# OSO-SCAP-A1-02_SAMD51_Sensor_Cap.net
KiCad netlist of a schematic drawn in EAGLE
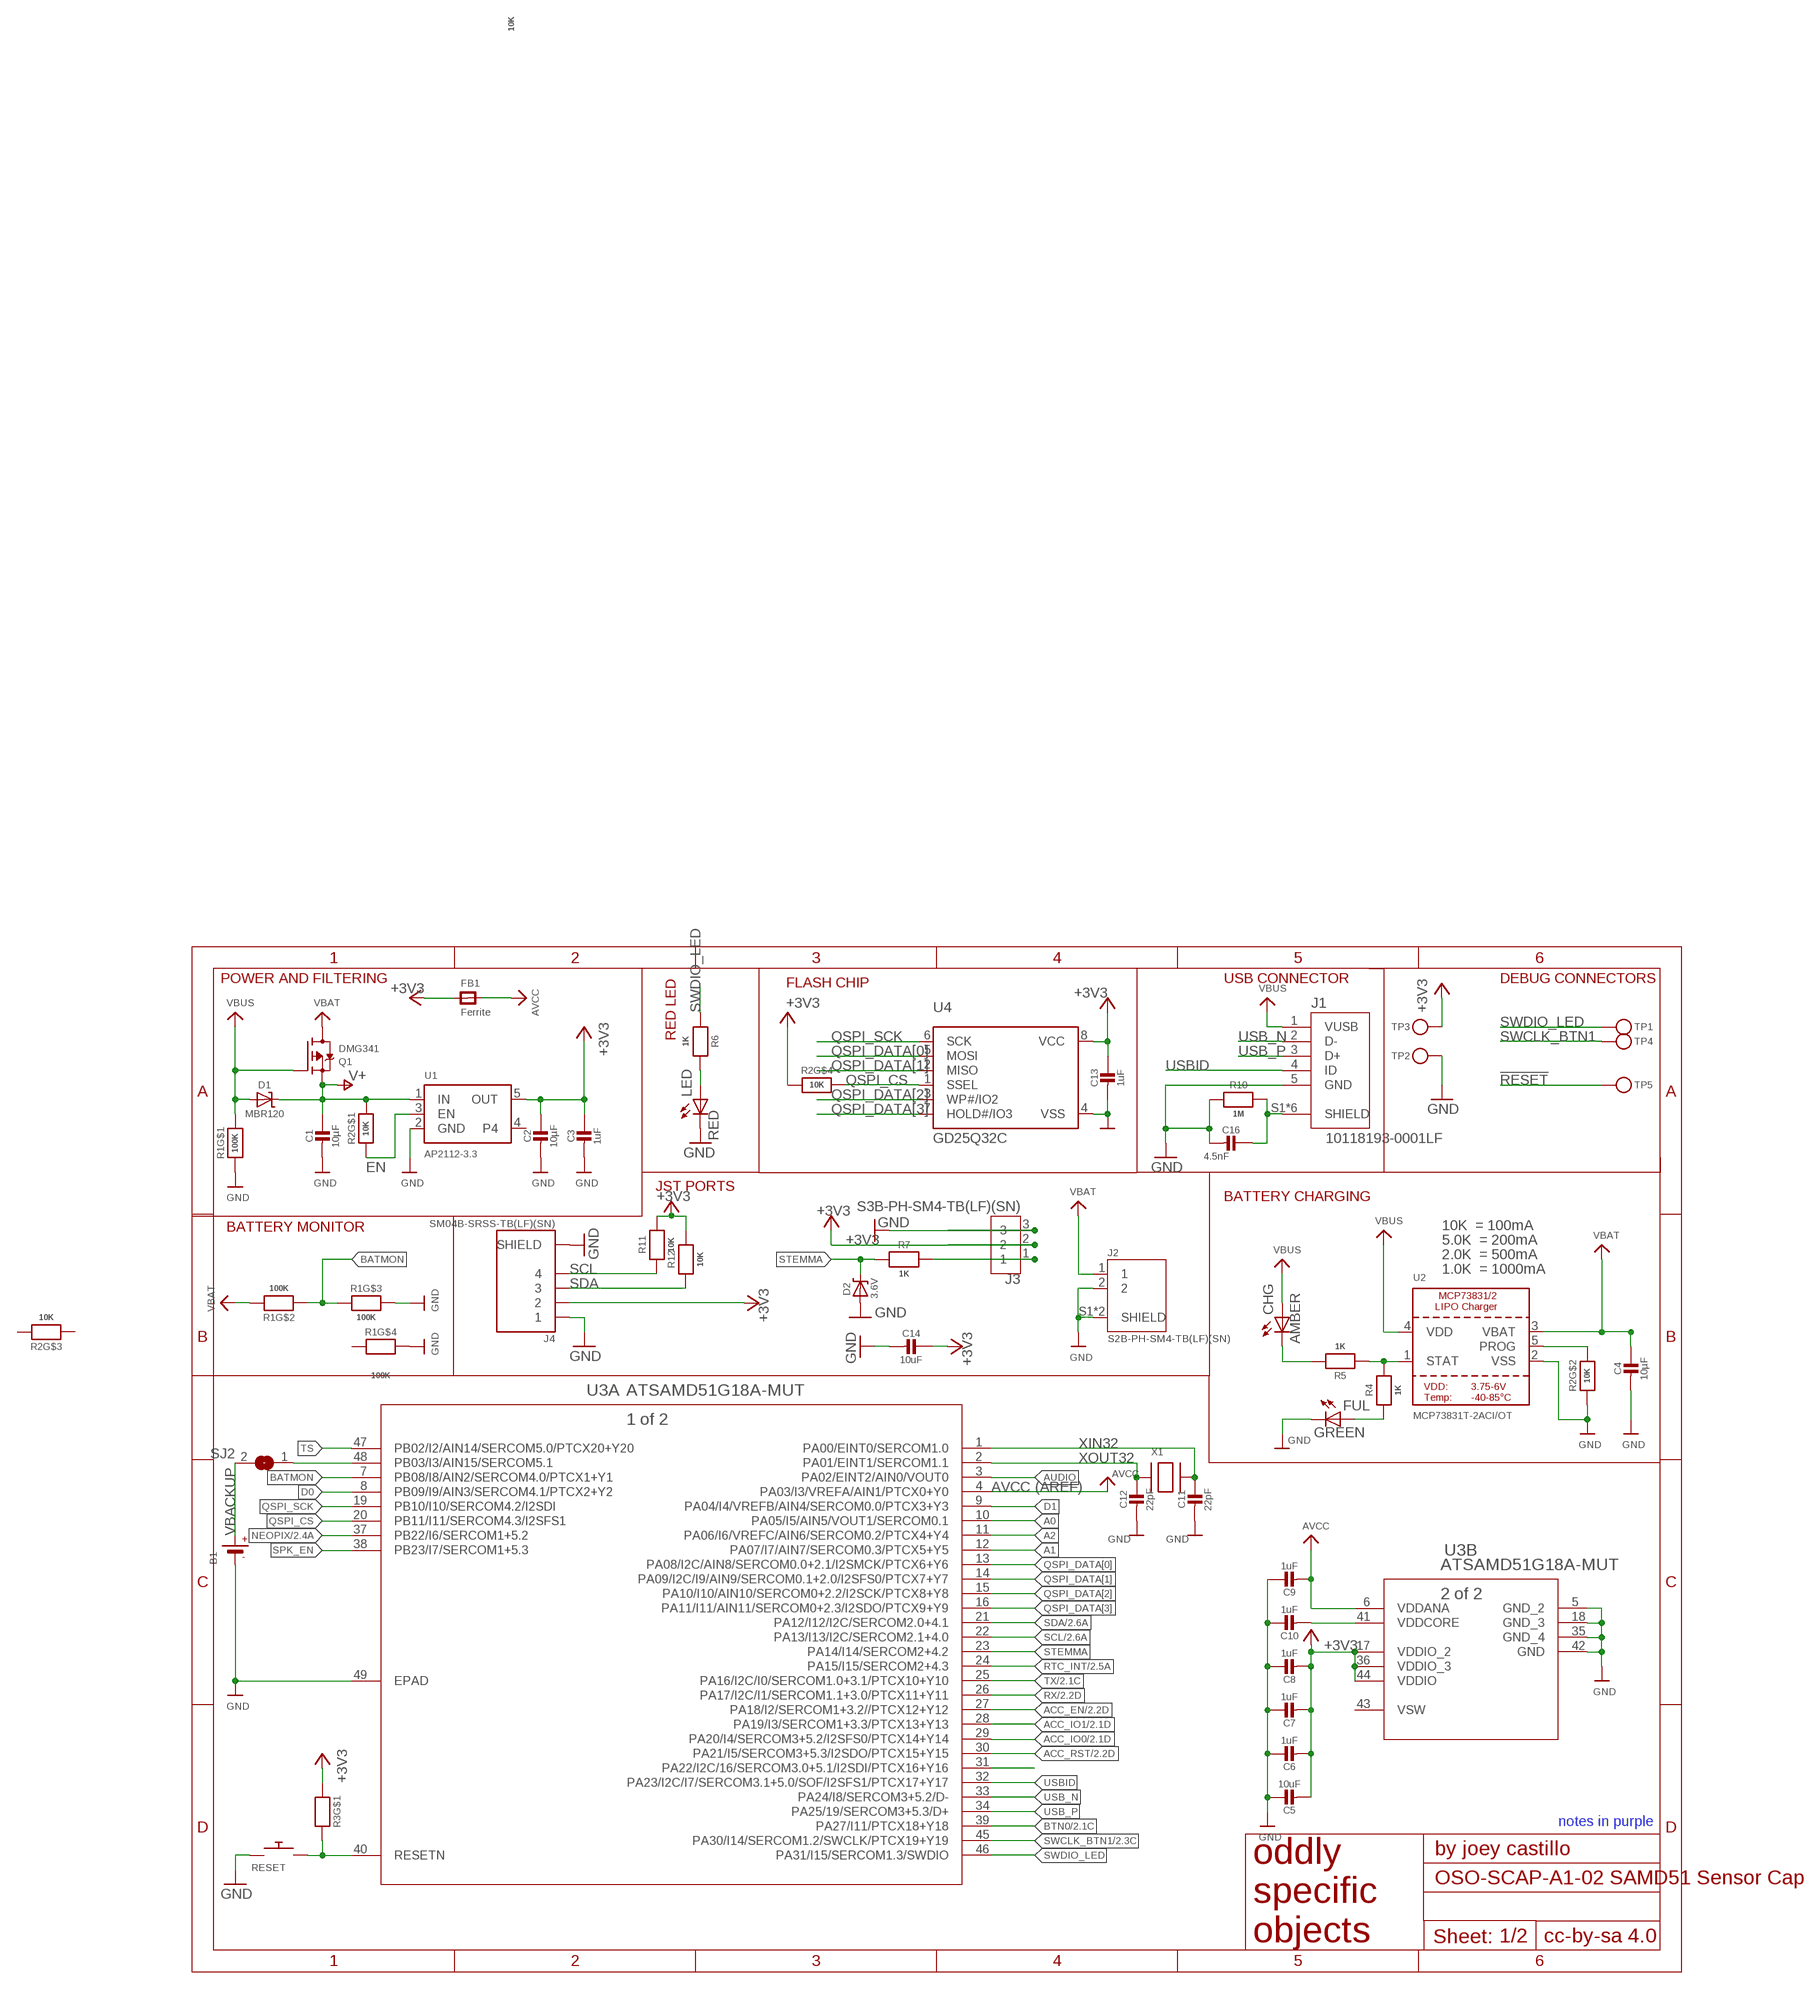
[diagram p0: schematic, sheet 1]
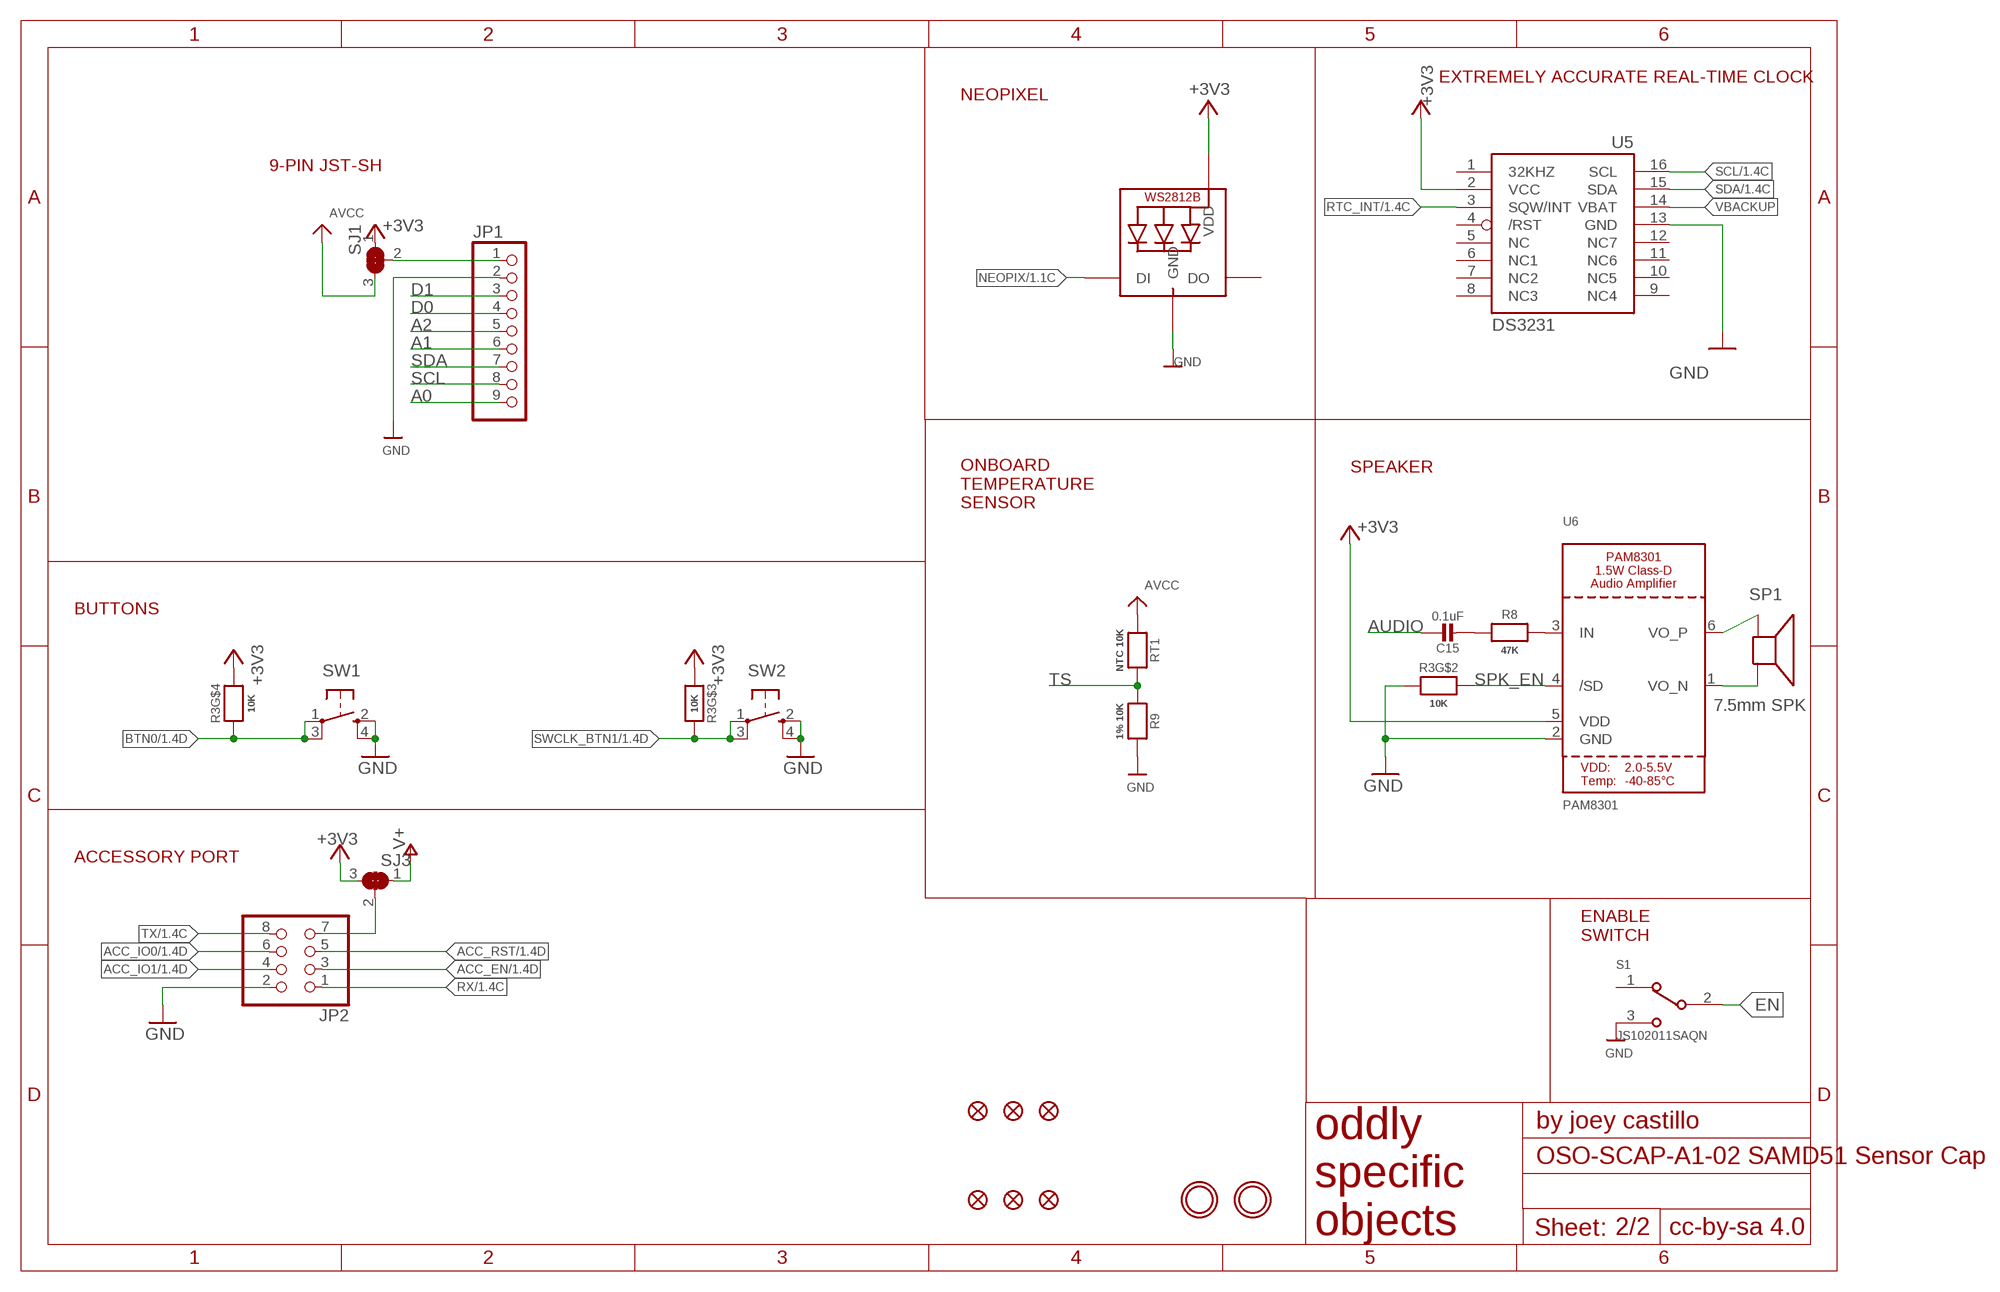
[diagram p1: schematic, sheet 2]

(export (version "E")
  (design (tool "Eeschema 10.0.6"))
  (components
    (comp (ref "B1")
      (value "CR1220")
      (footprint "eagle-import:CR1220-2")
      (libsource (lib "eagle-import") (part "BATTERYCR1220_2"))
    )
    (comp (ref "C1")
      (value "10µF")
      (footprint "eagle-import:0805-NO")
      (libsource (lib "eagle-import") (part "CAP_CERAMIC0805-NOOUTLINE"))
    )
    (comp (ref "C2")
      (value "10µF")
      (footprint "eagle-import:0805-NO")
      (libsource (lib "eagle-import") (part "CAP_CERAMIC0805-NOOUTLINE"))
    )
    (comp (ref "C3")
      (value "1uF")
      (footprint "eagle-import:0603-NO")
      (libsource (lib "eagle-import") (part "CAP_CERAMIC0603_NO"))
    )
    (comp (ref "C4")
      (value "10µF")
      (footprint "eagle-import:0805-NO")
      (libsource (lib "eagle-import") (part "CAP_CERAMIC0805-NOOUTLINE"))
    )
    (comp (ref "C5")
      (value "10uF")
      (footprint "eagle-import:0805_10MGAP")
      (libsource (lib "eagle-import") (part "CAP_CERAMIC0805_10MGAP"))
    )
    (comp (ref "C6")
      (value "1uF")
      (footprint "eagle-import:0603-NO")
      (libsource (lib "eagle-import") (part "CAP_CERAMIC0603_NO"))
    )
    (comp (ref "C7")
      (value "1uF")
      (footprint "eagle-import:0603-NO")
      (libsource (lib "eagle-import") (part "CAP_CERAMIC0603_NO"))
    )
    (comp (ref "C8")
      (value "1uF")
      (footprint "eagle-import:0603-NO")
      (libsource (lib "eagle-import") (part "CAP_CERAMIC0603_NO"))
    )
    (comp (ref "C9")
      (value "1uF")
      (footprint "eagle-import:0603-NO")
      (libsource (lib "eagle-import") (part "CAP_CERAMIC0603_NO"))
    )
    (comp (ref "C10")
      (value "1uF")
      (footprint "eagle-import:0603-NO")
      (libsource (lib "eagle-import") (part "CAP_CERAMIC0603_NO"))
    )
    (comp (ref "C11")
      (value "22pF")
      (footprint "eagle-import:0603-NO")
      (libsource (lib "eagle-import") (part "CAP_CERAMIC0603_NO"))
    )
    (comp (ref "C12")
      (value "22pF")
      (footprint "eagle-import:0603-NO")
      (libsource (lib "eagle-import") (part "CAP_CERAMIC0603_NO"))
    )
    (comp (ref "C13")
      (value "1uF")
      (footprint "eagle-import:0603-NO")
      (libsource (lib "eagle-import") (part "CAP_CERAMIC0603_NO"))
    )
    (comp (ref "C14")
      (value "10uF")
      (footprint "eagle-import:0805-NO")
      (libsource (lib "eagle-import") (part "CAP_CERAMIC0805-NOOUTLINE"))
    )
    (comp (ref "C16")
      (value "4.5nF")
      (footprint "eagle-import:0603-NO")
      (libsource (lib "eagle-import") (part "CAP_CERAMIC0603_NO"))
    )
    (comp (ref "CHG")
      (value "AMBER")
      (footprint "eagle-import:CHIPLED_0603")
      (libsource (lib "eagle-import") (part "LEDCHIPLED_0603"))
    )
    (comp (ref "D1")
      (value "MBR120")
      (footprint "eagle-import:SOD-123")
      (libsource (lib "eagle-import") (part "DIODE-SCHOTTKYSOD-123"))
    )
    (comp (ref "D2")
      (value "3.6V")
      (footprint "eagle-import:SOD-123")
      (libsource (lib "eagle-import") (part "DIODE-ZENERSOD123"))
    )
    (comp (ref "FB1")
      (value "Ferrite")
      (footprint "eagle-import:_0805MP")
      (libsource (lib "eagle-import") (part "FERRITE_0805MP"))
    )
    (comp (ref "FUL")
      (value "GREEN")
      (footprint "eagle-import:CHIPLED_0603")
      (libsource (lib "eagle-import") (part "LEDCHIPLED_0603"))
    )
    (comp (ref "J1")
      (value "10118193-0001LF")
      (footprint "eagle-import:FCI_10118193-0001LF")
      (fields (field (name "DIGI-KEY_PART_NUMBER") "609-4616-1-ND") (field (name "MF") "Amphenol ICC"))
      (libsource (lib "eagle-import") (part "10118193-0001LF"))
    )
    (comp (ref "J2")
      (value "S2B-PH-SM4-TB(LF)(SN)")
      (footprint "eagle-import:JST_S2B-PH-SM4-TB(LF)(SN)")
      (fields
        (field (name "DIGI-KEY_PART_NUMBER") "455-1749-1-ND")
        (field (name "MF") "JST Sales")
        (field (name "MP") "S2B-PH-SM4-TB_LF__SN_")
      )
      (libsource (lib "eagle-import") (part "S2B-PH-SM4-TB(LF)(SN)"))
    )
    (comp (ref "J3")
      (value "S3B-PH-SM4-TB(LF)(SN)")
      (footprint "eagle-import:JST_S3B-PH-SM4-TB(LF)(SN)")
      (fields
        (field (name "DIGI-KEY_PART_NUMBER") "455-1750-1-ND")
        (field (name "MF") "JST Sales")
        (field (name "MP") "S3B-PH-SM4-TB_LF__SN_")
      )
      (libsource (lib "eagle-import") (part "S3B-PH-SM4-TB(LF)(SN)"))
    )
    (comp (ref "J4")
      (value "SM04B-SRSS-TB(LF)(SN)")
      (footprint "eagle-import:JST_SM04B-SRSS-TB(LF)(SN)")
      (fields
        (field (name "DIGI-KEY_PART_NUMBER") "455-1804-1-ND")
        (field (name "MF") "JST Sales")
        (field (name "MP") "SM04B-SRSS-TB_LF__SN_")
      )
      (libsource (lib "eagle-import") (part "SM04B-SRSS-TB(LF)(SN)"))
    )
    (comp (ref "LED")
      (value "RED")
      (footprint "eagle-import:CHIPLED_0603")
      (libsource (lib "eagle-import") (part "LEDCHIPLED_0603"))
    )
    (comp (ref "Q1")
      (value "DMG341")
      (footprint "eagle-import:SOT23-R")
      (libsource (lib "eagle-import") (part "MOSFET-P"))
    )
    (comp (ref "R1")
      (value "100K")
      (footprint "eagle-import:EXBV8V")
      (fields (field (name "MANUFACTURER_PART_NUMBER") "EXBV8V103JV"))
      (libsource (lib "eagle-import") (part "EXB-V8V103JV-GOOD"))
    )
    (comp (ref "R2")
      (value "10K")
      (footprint "eagle-import:EXBV8V")
      (fields (field (name "MANUFACTURER_PART_NUMBER") "EXBV8V103JV"))
      (libsource (lib "eagle-import") (part "EXB-V8V103JV-GOOD"))
    )
    (comp (ref "R3")
      (value "10K")
      (footprint "eagle-import:EXBV8V")
      (fields (field (name "MANUFACTURER_PART_NUMBER") "EXBV8V103JV"))
      (libsource (lib "eagle-import") (part "EXB-V8V103JV-GOOD"))
    )
    (comp (ref "R4")
      (value "1K")
      (footprint "eagle-import:0603-NO")
      (libsource (lib "eagle-import") (part "RESISTOR_0603_NOOUT"))
    )
    (comp (ref "R5")
      (value "1K")
      (footprint "eagle-import:0603-NO")
      (libsource (lib "eagle-import") (part "RESISTOR_0603_NOOUT"))
    )
    (comp (ref "R6")
      (value "1K")
      (footprint "eagle-import:0603-NO")
      (libsource (lib "eagle-import") (part "RESISTOR_0603_NOOUT"))
    )
    (comp (ref "R7")
      (value "1K")
      (footprint "eagle-import:0603-NO")
      (libsource (lib "eagle-import") (part "RESISTOR_0603_NOOUT"))
    )
    (comp (ref "R10")
      (value "1M")
      (footprint "eagle-import:0603-NO")
      (libsource (lib "eagle-import") (part "RESISTOR_0603_NOOUT"))
    )
    (comp (ref "R11")
      (value "10K")
      (footprint "eagle-import:0603-NO")
      (libsource (lib "eagle-import") (part "RESISTOR_0603_NOOUT"))
    )
    (comp (ref "R12")
      (value "10K")
      (footprint "eagle-import:0603-NO")
      (libsource (lib "eagle-import") (part "RESISTOR_0603_NOOUT"))
    )
    (comp (ref "RESET")
      (value "SWITCH_PUSHBUTTONC&K_KSS")
      (footprint "eagle-import:BTN_CK_KSS")
      (libsource (lib "eagle-import") (part "SWITCH_PUSHBUTTONC&K_KSS"))
    )
    (comp (ref "SJ2")
      (value "SOLDERJUMPERREFLOW_NOPASTE")
      (footprint "eagle-import:SOLDERJUMPER_REFLOW_NOPASTE")
      (libsource (lib "eagle-import") (part "SOLDERJUMPERREFLOW_NOPASTE"))
    )
    (comp (ref "TP1")
      (value "TESTPOINTROUND1.5MMNO")
      (footprint "eagle-import:TESTPOINT_ROUND_1.5MM_NO")
      (libsource (lib "eagle-import") (part "TESTPOINTROUND1.5MMNO"))
    )
    (comp (ref "TP2")
      (value "TESTPOINTROUND1.5MMNO")
      (footprint "eagle-import:TESTPOINT_ROUND_1.5MM_NO")
      (libsource (lib "eagle-import") (part "TESTPOINTROUND1.5MMNO"))
    )
    (comp (ref "TP3")
      (value "TESTPOINTROUND1.5MMNO")
      (footprint "eagle-import:TESTPOINT_ROUND_1.5MM_NO")
      (libsource (lib "eagle-import") (part "TESTPOINTROUND1.5MMNO"))
    )
    (comp (ref "TP4")
      (value "TESTPOINTROUND1.5MMNO")
      (footprint "eagle-import:TESTPOINT_ROUND_1.5MM_NO")
      (libsource (lib "eagle-import") (part "TESTPOINTROUND1.5MMNO"))
    )
    (comp (ref "TP5")
      (value "TESTPOINTROUND1.5MMNO")
      (footprint "eagle-import:TESTPOINT_ROUND_1.5MM_NO")
      (libsource (lib "eagle-import") (part "TESTPOINTROUND1.5MMNO"))
    )
    (comp (ref "U1")
      (value "AP2112-3.3")
      (footprint "eagle-import:SOT23-5")
      (libsource (lib "eagle-import") (part "VREG_SOT23-5"))
    )
    (comp (ref "U2")
      (value "MCP73831T-2ACI/OT")
      (footprint "eagle-import:SOT23-5")
      (libsource (lib "eagle-import") (part "MCP73831/2"))
    )
    (comp (ref "U3")
      (value "ATSAMD51G18A-MUT")
      (footprint "eagle-import:QFN48_7X7MC")
      (fields (field (name "COPYRIGHT") "Copyright (C) 2018 Accelerated Designs. All rights reserved"))
      (libsource (lib "eagle-import") (part "ATSAMD51G18A-MUT"))
    )
    (comp (ref "U4")
      (value "GD25Q32C")
      (footprint "eagle-import:MICROBUILDER_SOIC8_150MIL")
      (libsource (lib "eagle-import") (part "MICROBUILDER_SPIFLASH_SOIC8"))
    )
    (comp (ref "X1")
      (value "XTAL-3.2X1.5")
      (footprint "eagle-import:XTAL3215")
      (libsource (lib "eagle-import") (part "XTAL-3.2X1.5"))
    )
    (comp (ref "C15")
      (value "0.1uF")
      (footprint "eagle-import:0603-NO")
      (libsource (lib "eagle-import") (part "CAP_CERAMIC0603_NO"))
    )
    (comp (ref "FID1")
      (value "FIDUCIAL_1MM")
      (footprint "eagle-import:FIDUCIAL_1MM")
      (libsource (lib "eagle-import") (part "FIDUCIAL_1MM"))
    )
    (comp (ref "FID2")
      (value "FIDUCIAL_1MM")
      (footprint "eagle-import:FIDUCIAL_1MM")
      (libsource (lib "eagle-import") (part "FIDUCIAL_1MM"))
    )
    (comp (ref "FID3")
      (value "FIDUCIAL_1MM")
      (footprint "eagle-import:FIDUCIAL_1MM")
      (libsource (lib "eagle-import") (part "FIDUCIAL_1MM"))
    )
    (comp (ref "FID4")
      (value "FIDUCIAL_1MM")
      (footprint "eagle-import:FIDUCIAL_1MM")
      (libsource (lib "eagle-import") (part "FIDUCIAL_1MM"))
    )
    (comp (ref "FID5")
      (value "FIDUCIAL_1MM")
      (footprint "eagle-import:FIDUCIAL_1MM")
      (libsource (lib "eagle-import") (part "FIDUCIAL_1MM"))
    )
    (comp (ref "FID6")
      (value "FIDUCIAL_1MM")
      (footprint "eagle-import:FIDUCIAL_1MM")
      (libsource (lib "eagle-import") (part "FIDUCIAL_1MM"))
    )
    (comp (ref "JP1")
      (value "HEADER-1X9_JSTSH")
      (footprint "eagle-import:JST_SH9")
      (libsource (lib "eagle-import") (part "HEADER-1X9_JSTSH"))
    )
    (comp (ref "JP2")
      (value "PINHD-2X4SMT")
      (footprint "eagle-import:PINHD_2X4_SMT")
      (libsource (lib "eagle-import") (part "PINHD-2X4SMT"))
    )
    (comp (ref "NEOPIX")
      (value "WS2812B_4020")
      (footprint "eagle-import:WS2812B_4020")
      (libsource (lib "eagle-import") (part "WS2812B_4020"))
    )
    (comp (ref "R8")
      (value "47K")
      (footprint "eagle-import:0603-NO")
      (libsource (lib "eagle-import") (part "RESISTOR_0603_NOOUT"))
    )
    (comp (ref "R9")
      (value "1% 10K")
      (footprint "eagle-import:0805-NO")
      (libsource (lib "eagle-import") (part "RESISTOR0805_NOOUTLINE"))
    )
    (comp (ref "RT1")
      (value "NTC 10K")
      (footprint "eagle-import:0805-NO")
      (libsource (lib "eagle-import") (part "RESISTOR0805_NOOUTLINE"))
    )
    (comp (ref "S1")
      (value "JS102011SAQN")
      (footprint "eagle-import:SW_JS102011SAQN")
      (fields (field (name "DIGI-KEY_PART_NUMBER") "401-1999-1-ND") (field (name "MF") "C&K"))
      (libsource (lib "eagle-import") (part "JS102011SAQN"))
    )
    (comp (ref "SJ1")
      (value "SOLDERJUMPER_2WAY")
      (footprint "eagle-import:SOLDERJUMPER_2WAY_OPEN_NOPASTE")
      (libsource (lib "eagle-import") (part "SOLDERJUMPER_2WAY"))
    )
    (comp (ref "SJ3")
      (value "SOLDERJUMPER_2WAY")
      (footprint "eagle-import:SOLDERJUMPER_2WAY_OPEN_NOPASTE")
      (libsource (lib "eagle-import") (part "SOLDERJUMPER_2WAY"))
    )
    (comp (ref "SP1")
      (value "7.5mm SPK")
      (footprint "eagle-import:BUZZER_SMT_5MM")
      (libsource (lib "eagle-import") (part "SPEAKER_BUZZER5MM"))
    )
    (comp (ref "SW1")
      (value "SPST_TACT-KMR2")
      (footprint "eagle-import:KMR2")
      (libsource (lib "eagle-import") (part "SPST_TACT-KMR2"))
    )
    (comp (ref "SW2")
      (value "SPST_TACT-KMR2")
      (footprint "eagle-import:KMR2")
      (libsource (lib "eagle-import") (part "SPST_TACT-KMR2"))
    )
    (comp (ref "U$1")
      (value "MOUNTINGHOLE2.5")
      (footprint "eagle-import:MOUNTINGHOLE_2.5_PLATED")
      (libsource (lib "eagle-import") (part "MOUNTINGHOLE2.5"))
    )
    (comp (ref "U$4")
      (value "MOUNTINGHOLE2.5")
      (footprint "eagle-import:MOUNTINGHOLE_2.5_PLATED")
      (libsource (lib "eagle-import") (part "MOUNTINGHOLE2.5"))
    )
    (comp (ref "U5")
      (value "DS3231/SO")
      (footprint "eagle-import:SO16W")
      (libsource (lib "eagle-import") (part "DS3231/SO"))
    )
    (comp (ref "U6")
      (value "PAM8301")
      (footprint "eagle-import:SOT23-6")
      (libsource (lib "eagle-import") (part "PAM8301"))
    )
  )
  (nets
    (net (code "1") (name "+3V3") (class "Default")
      (node (ref "C13") (pin "1") (pinfunction "1_1") (pintype "passive"))
      (node (ref "C14") (pin "1") (pinfunction "1_1") (pintype "passive"))
      (node (ref "C2") (pin "1") (pinfunction "1_1") (pintype "passive"))
      (node (ref "C3") (pin "1") (pinfunction "1_1") (pintype "passive"))
      (node (ref "C5") (pin "2") (pinfunction "2_2") (pintype "passive"))
      (node (ref "C6") (pin "2") (pinfunction "2_2") (pintype "passive"))
      (node (ref "C7") (pin "2") (pinfunction "2_2") (pintype "passive"))
      (node (ref "C8") (pin "2") (pinfunction "2_2") (pintype "passive"))
      (node (ref "FB1") (pin "1") (pinfunction "P$1_1") (pintype "passive"))
      (node (ref "J3") (pin "2") (pinfunction "2_2") (pintype "passive"))
      (node (ref "J4") (pin "2") (pinfunction "2_2") (pintype "passive"))
      (node (ref "NEOPIX") (pin "2") (pinfunction "VDD_2") (pintype "power_in"))
      (node (ref "R11") (pin "2") (pinfunction "2_2") (pintype "passive"))
      (node (ref "R12") (pin "2") (pinfunction "2_2") (pintype "passive"))
      (node (ref "R2") (pin "4") (pinfunction "1_4") (pintype "passive"))
      (node (ref "R3") (pin "1") (pinfunction "1_1") (pintype "passive"))
      (node (ref "R3") (pin "3") (pinfunction "1_3") (pintype "passive"))
      (node (ref "R3") (pin "5") (pinfunction "2_5") (pintype "passive"))
      (node (ref "SJ1") (pin "1") (pinfunction "1_1") (pintype "passive"))
      (node (ref "SJ3") (pin "3") (pinfunction "3_3") (pintype "passive"))
      (node (ref "TP3") (pin "P$1") (pinfunction "P$1_P$1") (pintype "bidirectional"))
      (node (ref "U1") (pin "5") (pinfunction "OUT_5") (pintype "power_in"))
      (node (ref "U3") (pin "17") (pinfunction "VDDIO_2_17") (pintype "power_in"))
      (node (ref "U3") (pin "36") (pinfunction "VDDIO_3_36") (pintype "power_in"))
      (node (ref "U3") (pin "44") (pinfunction "VDDIO_44") (pintype "power_in"))
      (node (ref "U4") (pin "8") (pinfunction "VCC_8") (pintype "bidirectional"))
      (node (ref "U5") (pin "2") (pinfunction "VCC_2") (pintype "power_in"))
      (node (ref "U6") (pin "5") (pinfunction "VDD_5") (pintype "power_in"))
    )
    (net (code "2") (name "A0") (class "Default")
      (node (ref "JP1") (pin "9") (pinfunction "9_9") (pintype "passive"))
      (node (ref "U3") (pin "10") (pinfunction "PA05/I5/AIN5/VOUT1/SERCOM0.1_10") (pintype "bidirectional"))
    )
    (net (code "3") (name "A1") (class "Default")
      (node (ref "JP1") (pin "6") (pinfunction "6_6") (pintype "passive"))
      (node (ref "U3") (pin "12") (pinfunction "PA07/I7/AIN7/SERCOM0.3/PTCX5+Y5_12") (pintype "bidirectional"))
    )
    (net (code "4") (name "A2") (class "Default")
      (node (ref "JP1") (pin "5") (pinfunction "5_5") (pintype "passive"))
      (node (ref "U3") (pin "11") (pinfunction "PA06/I6/VREFC/AIN6/SERCOM0.2/PTCX4+Y4_11") (pintype "bidirectional"))
    )
    (net (code "5") (name "ACC_EN") (class "Default")
      (node (ref "JP2") (pin "3") (pinfunction "3_3") (pintype "passive"))
      (node (ref "U3") (pin "27") (pinfunction "PA18/I2/SERCOM1+3.2//PTCX12+Y12_27") (pintype "bidirectional"))
    )
    (net (code "6") (name "ACC_IO0") (class "Default")
      (node (ref "JP2") (pin "6") (pinfunction "6_6") (pintype "passive"))
      (node (ref "U3") (pin "29") (pinfunction "PA20/I4/SERCOM3+5.2/I2SFS0/PTCX14+Y14_29") (pintype "bidirectional"))
    )
    (net (code "7") (name "ACC_IO1") (class "Default")
      (node (ref "JP2") (pin "4") (pinfunction "4_4") (pintype "passive"))
      (node (ref "U3") (pin "28") (pinfunction "PA19/I3/SERCOM1+3.3/PTCX13+Y13_28") (pintype "bidirectional"))
    )
    (net (code "8") (name "ACC_RST") (class "Default")
      (node (ref "JP2") (pin "5") (pinfunction "5_5") (pintype "passive"))
      (node (ref "U3") (pin "30") (pinfunction "PA21/I5/SERCOM3+5.3/I2SDO/PTCX15+Y15_30") (pintype "bidirectional"))
    )
    (net (code "9") (name "AUDIO") (class "Default")
      (node (ref "C15") (pin "1") (pinfunction "1_1") (pintype "passive"))
      (node (ref "U3") (pin "3") (pinfunction "PA02/EINT2/AIN0/VOUT0_3") (pintype "bidirectional"))
    )
    (net (code "10") (name "AVCC") (class "Default")
      (node (ref "C9") (pin "2") (pinfunction "2_2") (pintype "passive"))
      (node (ref "FB1") (pin "2") (pinfunction "P$2_2") (pintype "passive"))
      (node (ref "RT1") (pin "1") (pinfunction "1_1") (pintype "passive"))
      (node (ref "SJ1") (pin "3") (pinfunction "3_3") (pintype "passive"))
      (node (ref "U3") (pin "4") (pinfunction "PA03/I3/VREFA/AIN1/PTCX0+Y0_4") (pintype "bidirectional"))
      (node (ref "U3") (pin "6") (pinfunction "VDDANA_6") (pintype "power_in"))
    )
    (net (code "11") (name "BATMON") (class "Default")
      (node (ref "R1") (pin "2") (pinfunction "1_2") (pintype "passive"))
      (node (ref "R1") (pin "3") (pinfunction "1_3") (pintype "passive"))
      (node (ref "U3") (pin "7") (pinfunction "PB08/I8/AIN2/SERCOM4.0/PTCX1+Y1_7") (pintype "bidirectional"))
    )
    (net (code "12") (name "BTN0") (class "Default")
      (node (ref "R3") (pin "4") (pinfunction "1_4") (pintype "passive"))
      (node (ref "SW1") (pin "1") (pinfunction "P_1") (pintype "passive"))
      (node (ref "SW1") (pin "3") (pinfunction "P1_3") (pintype "passive"))
      (node (ref "U3") (pin "39") (pinfunction "PA27/I11/PTCX18+Y18_39") (pintype "bidirectional"))
    )
    (net (code "13") (name "D0") (class "Default")
      (node (ref "JP1") (pin "4") (pinfunction "4_4") (pintype "passive"))
      (node (ref "U3") (pin "8") (pinfunction "PB09/I9/AIN3/SERCOM4.1/PTCX2+Y2_8") (pintype "bidirectional"))
    )
    (net (code "14") (name "D1") (class "Default")
      (node (ref "JP1") (pin "3") (pinfunction "3_3") (pintype "passive"))
      (node (ref "U3") (pin "9") (pinfunction "PA04/I4/VREFB/AIN4/SERCOM0.0/PTCX3+Y3_9") (pintype "bidirectional"))
    )
    (net (code "15") (name "EN") (class "Default")
      (node (ref "R2") (pin "1") (pinfunction "1_1") (pintype "passive"))
      (node (ref "S1") (pin "2") (pinfunction "2_2") (pintype "passive"))
      (node (ref "U1") (pin "3") (pinfunction "EN_3") (pintype "input"))
    )
    (net (code "16") (name "GND") (class "Default")
      (node (ref "B1") (pin "-") (pinfunction "-_-") (pintype "passive"))
      (node (ref "C1") (pin "2") (pinfunction "2_2") (pintype "passive"))
      (node (ref "C10") (pin "1") (pinfunction "1_1") (pintype "passive"))
      (node (ref "C11") (pin "2") (pinfunction "2_2") (pintype "passive"))
      (node (ref "C12") (pin "2") (pinfunction "2_2") (pintype "passive"))
      (node (ref "C13") (pin "2") (pinfunction "2_2") (pintype "passive"))
      (node (ref "C14") (pin "2") (pinfunction "2_2") (pintype "passive"))
      (node (ref "C16") (pin "2") (pinfunction "2_2") (pintype "passive"))
      (node (ref "C2") (pin "2") (pinfunction "2_2") (pintype "passive"))
      (node (ref "C3") (pin "2") (pinfunction "2_2") (pintype "passive"))
      (node (ref "C4") (pin "2") (pinfunction "2_2") (pintype "passive"))
      (node (ref "C5") (pin "1") (pinfunction "1_1") (pintype "passive"))
      (node (ref "C6") (pin "1") (pinfunction "1_1") (pintype "passive"))
      (node (ref "C7") (pin "1") (pinfunction "1_1") (pintype "passive"))
      (node (ref "C8") (pin "1") (pinfunction "1_1") (pintype "passive"))
      (node (ref "C9") (pin "1") (pinfunction "1_1") (pintype "passive"))
      (node (ref "D2") (pin "A") (pinfunction "A_A") (pintype "passive"))
      (node (ref "FUL") (pin "C") (pinfunction "C_C") (pintype "passive"))
      (node (ref "J1") (pin "5") (pinfunction "GND_5") (pintype "passive"))
      (node (ref "J2") (pin "2") (pinfunction "2_2") (pintype "passive"))
      (node (ref "J2") (pin "S1") (pinfunction "SHIELD_S1") (pintype "passive"))
      (node (ref "J2") (pin "S2") (pinfunction "SHIELD_S2") (pintype "passive"))
      (node (ref "J3") (pin "3") (pinfunction "3_3") (pintype "passive"))
      (node (ref "J4") (pin "1") (pinfunction "1_1") (pintype "passive"))
      (node (ref "J4") (pin "S1") (pinfunction "SHIELD_S1") (pintype "passive"))
      (node (ref "J4") (pin "S2") (pinfunction "SHIELD_S2") (pintype "passive"))
      (node (ref "JP1") (pin "2") (pinfunction "2_2") (pintype "passive"))
      (node (ref "JP2") (pin "2") (pinfunction "2_2") (pintype "passive"))
      (node (ref "LED") (pin "C") (pinfunction "C_C") (pintype "passive"))
      (node (ref "NEOPIX") (pin "4") (pinfunction "GND_4") (pintype "power_in"))
      (node (ref "R1") (pin "1") (pinfunction "1_1") (pintype "passive"))
      (node (ref "R1") (pin "5") (pinfunction "2_5") (pintype "passive"))
      (node (ref "R1") (pin "6") (pinfunction "2_6") (pintype "passive"))
      (node (ref "R10") (pin "2") (pinfunction "2_2") (pintype "passive"))
      (node (ref "R2") (pin "2") (pinfunction "1_2") (pintype "passive"))
      (node (ref "R3") (pin "2") (pinfunction "1_2") (pintype "passive"))
      (node (ref "R9") (pin "2") (pinfunction "2_2") (pintype "passive"))
      (node (ref "RESET") (pin "P$1") (pinfunction "P$1_P$1") (pintype "passive"))
      (node (ref "S1") (pin "3") (pinfunction "3_3") (pintype "passive"))
      (node (ref "SW1") (pin "2") (pinfunction "S_2") (pintype "passive"))
      (node (ref "SW1") (pin "4") (pinfunction "S1_4") (pintype "passive"))
      (node (ref "SW2") (pin "2") (pinfunction "S_2") (pintype "passive"))
      (node (ref "SW2") (pin "4") (pinfunction "S1_4") (pintype "passive"))
      (node (ref "TP2") (pin "P$1") (pinfunction "P$1_P$1") (pintype "bidirectional"))
      (node (ref "U1") (pin "2") (pinfunction "GND_2") (pintype "power_in"))
      (node (ref "U2") (pin "2") (pinfunction "VSS_2") (pintype "power_in"))
      (node (ref "U3") (pin "18") (pinfunction "GND_3_18") (pintype "passive"))
      (node (ref "U3") (pin "35") (pinfunction "GND_4_35") (pintype "passive"))
      (node (ref "U3") (pin "42") (pinfunction "GND_42") (pintype "passive"))
      (node (ref "U3") (pin "49") (pinfunction "EPAD_49") (pintype "passive"))
      (node (ref "U3") (pin "5") (pinfunction "GND_2_5") (pintype "passive"))
      (node (ref "U4") (pin "4") (pinfunction "VSS_4") (pintype "bidirectional"))
      (node (ref "U5") (pin "13") (pinfunction "GND_13") (pintype "power_in"))
      (node (ref "U6") (pin "2") (pinfunction "GND_2") (pintype "power_in"))
    )
    (net (code "17") (name "NEOPIX") (class "Default")
      (node (ref "NEOPIX") (pin "1") (pinfunction "DI_1") (pintype "input"))
      (node (ref "U3") (pin "37") (pinfunction "PB22/I6/SERCOM1+5.2_37") (pintype "bidirectional"))
    )
    (net (code "18") (name "Net-(C15-Pad2)") (class "Default")
      (node (ref "C15") (pin "2") (pinfunction "2_2") (pintype "passive"))
      (node (ref "R8") (pin "1") (pinfunction "1_1") (pintype "passive"))
    )
    (net (code "19") (name "Net-(C16-Pad1)") (class "Default")
      (node (ref "C16") (pin "1") (pinfunction "1_1") (pintype "passive"))
      (node (ref "J1") (pin "S1") (pinfunction "SHIELD_S1") (pintype "passive"))
      (node (ref "J1") (pin "S2") (pinfunction "SHIELD_S2") (pintype "passive"))
      (node (ref "J1") (pin "S3") (pinfunction "SHIELD_S3") (pintype "passive"))
      (node (ref "J1") (pin "S4") (pinfunction "SHIELD_S4") (pintype "passive"))
      (node (ref "J1") (pin "S5") (pinfunction "SHIELD_S5") (pintype "passive"))
      (node (ref "J1") (pin "S6") (pinfunction "SHIELD_S6") (pintype "passive"))
      (node (ref "R10") (pin "1") (pinfunction "1_1") (pintype "passive"))
    )
    (net (code "20") (name "Net-(CHG-PadC)") (class "Default")
      (node (ref "CHG") (pin "C") (pinfunction "C_C") (pintype "passive"))
      (node (ref "R5") (pin "2") (pinfunction "2_2") (pintype "passive"))
    )
    (net (code "21") (name "Net-(FUL-PadA)") (class "Default")
      (node (ref "FUL") (pin "A") (pinfunction "A_A") (pintype "passive"))
      (node (ref "R4") (pin "1") (pinfunction "1_1") (pintype "passive"))
    )
    (net (code "22") (name "Net-(J3-Pad1)") (class "Default")
      (node (ref "J3") (pin "1") (pinfunction "1_1") (pintype "passive"))
      (node (ref "R7") (pin "1") (pinfunction "1_1") (pintype "passive"))
    )
    (net (code "23") (name "Net-(JP1-Pad1)") (class "Default")
      (node (ref "JP1") (pin "1") (pinfunction "1_1") (pintype "passive"))
      (node (ref "SJ1") (pin "2") (pinfunction "2_2") (pintype "passive"))
    )
    (net (code "24") (name "Net-(JP2-Pad7)") (class "Default")
      (node (ref "JP2") (pin "7") (pinfunction "7_7") (pintype "passive"))
      (node (ref "SJ3") (pin "2") (pinfunction "2_2") (pintype "passive"))
    )
    (net (code "25") (name "Net-(LED-PadA)") (class "Default")
      (node (ref "LED") (pin "A") (pinfunction "A_A") (pintype "passive"))
      (node (ref "R6") (pin "2") (pinfunction "2_2") (pintype "passive"))
    )
    (net (code "26") (name "Net-(R2B-2)") (class "Default")
      (node (ref "R2") (pin "7") (pinfunction "2_7") (pintype "passive"))
      (node (ref "U2") (pin "5") (pinfunction "PROG_5") (pintype "input"))
    )
    (net (code "27") (name "Net-(U2-STAT)") (class "Default")
      (node (ref "R4") (pin "2") (pinfunction "2_2") (pintype "passive"))
      (node (ref "R5") (pin "1") (pinfunction "1_1") (pintype "passive"))
      (node (ref "U2") (pin "1") (pinfunction "STAT_1") (pintype "output"))
    )
    (net (code "28") (name "Net-(U3A-PB03{slash}I3{slash}AIN15{slash}SERCOM5.1)") (class "Default")
      (node (ref "SJ2") (pin "1") (pinfunction "1_1") (pintype "passive"))
      (node (ref "U3") (pin "48") (pinfunction "PB03/I3/AIN15/SERCOM5.1_48") (pintype "bidirectional"))
    )
    (net (code "29") (name "Net-(U3B-VDDCORE)") (class "Default")
      (node (ref "C10") (pin "2") (pinfunction "2_2") (pintype "passive"))
      (node (ref "U3") (pin "41") (pinfunction "VDDCORE_41") (pintype "bidirectional"))
    )
    (net (code "30") (name "Net-(U6-IN)") (class "Default")
      (node (ref "R8") (pin "2") (pinfunction "2_2") (pintype "passive"))
      (node (ref "U6") (pin "3") (pinfunction "IN_3") (pintype "input"))
    )
    (net (code "31") (name "Net-(U6-VO_N)") (class "Default")
      (node (ref "SP1") (pin "+") (pinfunction "+_+") (pintype "passive"))
      (node (ref "U6") (pin "1") (pinfunction "VO_N_1") (pintype "output"))
    )
    (net (code "32") (name "Net-(U6-VO_P)") (class "Default")
      (node (ref "SP1") (pin "-") (pinfunction "-_-") (pintype "passive"))
      (node (ref "U6") (pin "6") (pinfunction "VO_P_6") (pintype "output"))
    )
    (net (code "33") (name "QSPI_CS") (class "Default")
      (node (ref "R2") (pin "5") (pinfunction "2_5") (pintype "passive"))
      (node (ref "U3") (pin "20") (pinfunction "PB11/I11/SERCOM4.3/I2SFS1_20") (pintype "bidirectional"))
      (node (ref "U4") (pin "1") (pinfunction "SSEL_1") (pintype "bidirectional"))
    )
    (net (code "34") (name "QSPI_DATA[0]") (class "Default")
      (node (ref "U3") (pin "13") (pinfunction "PA08/I2C/AIN8/SERCOM0.0+2.1/I2SMCK/PTCX6+Y6_13") (pintype "bidirectional"))
      (node (ref "U4") (pin "5") (pinfunction "MOSI_5") (pintype "bidirectional"))
    )
    (net (code "35") (name "QSPI_DATA[1]") (class "Default")
      (node (ref "U3") (pin "14") (pinfunction "PA09/I2C/I9/AIN9/SERCOM0.1+2.0/I2SFS0/PTCX7+Y7_14") (pintype "bidirectional"))
      (node (ref "U4") (pin "2") (pinfunction "MISO_2") (pintype "bidirectional"))
    )
    (net (code "36") (name "QSPI_DATA[2]") (class "Default")
      (node (ref "U3") (pin "15") (pinfunction "PA10/I10/AIN10/SERCOM0+2.2/I2SCK/PTCX8+Y8_15") (pintype "bidirectional"))
      (node (ref "U4") (pin "3") (pinfunction "WP#/IO2_3") (pintype "bidirectional"))
    )
    (net (code "37") (name "QSPI_DATA[3]") (class "Default")
      (node (ref "U3") (pin "16") (pinfunction "PA11/I11/AIN11/SERCOM0+2.3/I2SDO/PTCX9+Y9_16") (pintype "bidirectional"))
      (node (ref "U4") (pin "7") (pinfunction "HOLD#/IO3_7") (pintype "bidirectional"))
    )
    (net (code "38") (name "QSPI_SCK") (class "Default")
      (node (ref "U3") (pin "19") (pinfunction "PB10/I10/SERCOM4.2/I2SDI_19") (pintype "bidirectional"))
      (node (ref "U4") (pin "6") (pinfunction "SCK_6") (pintype "bidirectional"))
    )
    (net (code "39") (name "RTC_INT") (class "Default")
      (node (ref "U3") (pin "24") (pinfunction "PA15/I15/SERCOM2+4.3_24") (pintype "bidirectional"))
      (node (ref "U5") (pin "3") (pinfunction "SQW/INT_3") (pintype "output"))
    )
    (net (code "40") (name "RX") (class "Default")
      (node (ref "JP2") (pin "1") (pinfunction "1_1") (pintype "passive"))
      (node (ref "U3") (pin "26") (pinfunction "PA17/I2C/I1/SERCOM1.1+3.0/PTCX11+Y11_26") (pintype "bidirectional"))
    )
    (net (code "41") (name "SCL") (class "Default")
      (node (ref "J4") (pin "4") (pinfunction "4_4") (pintype "passive"))
      (node (ref "JP1") (pin "8") (pinfunction "8_8") (pintype "passive"))
      (node (ref "R11") (pin "1") (pinfunction "1_1") (pintype "passive"))
      (node (ref "U3") (pin "22") (pinfunction "PA13/I13/I2C/SERCOM2.1+4.0_22") (pintype "bidirectional"))
      (node (ref "U5") (pin "16") (pinfunction "SCL_16") (pintype "bidirectional"))
    )
    (net (code "42") (name "SDA") (class "Default")
      (node (ref "J4") (pin "3") (pinfunction "3_3") (pintype "passive"))
      (node (ref "JP1") (pin "7") (pinfunction "7_7") (pintype "passive"))
      (node (ref "R12") (pin "1") (pinfunction "1_1") (pintype "passive"))
      (node (ref "U3") (pin "21") (pinfunction "PA12/I12/I2C/SERCOM2.0+4.1_21") (pintype "bidirectional"))
      (node (ref "U5") (pin "15") (pinfunction "SDA_15") (pintype "bidirectional"))
    )
    (net (code "43") (name "SPK_EN") (class "Default")
      (node (ref "R3") (pin "7") (pinfunction "2_7") (pintype "passive"))
      (node (ref "U3") (pin "38") (pinfunction "PB23/I7/SERCOM1+5.3_38") (pintype "bidirectional"))
      (node (ref "U6") (pin "4") (pinfunction "/SD_4") (pintype "input"))
    )
    (net (code "44") (name "STEMMA") (class "Default")
      (node (ref "D2") (pin "C") (pinfunction "C_C") (pintype "passive"))
      (node (ref "R7") (pin "2") (pinfunction "2_2") (pintype "passive"))
      (node (ref "U3") (pin "23") (pinfunction "PA14/I14/SERCOM2+4.2_23") (pintype "bidirectional"))
    )
    (net (code "45") (name "SWCLK_BTN1") (class "Default")
      (node (ref "R3") (pin "6") (pinfunction "2_6") (pintype "passive"))
      (node (ref "SW2") (pin "1") (pinfunction "P_1") (pintype "passive"))
      (node (ref "SW2") (pin "3") (pinfunction "P1_3") (pintype "passive"))
      (node (ref "TP4") (pin "P$1") (pinfunction "P$1_P$1") (pintype "bidirectional"))
      (node (ref "U3") (pin "45") (pinfunction "PA30/I14/SERCOM1.2/SWCLK/PTCX19+Y19_45") (pintype "bidirectional"))
    )
    (net (code "46") (name "SWDIO_LED") (class "Default")
      (node (ref "R6") (pin "1") (pinfunction "1_1") (pintype "passive"))
      (node (ref "TP1") (pin "P$1") (pinfunction "P$1_P$1") (pintype "bidirectional"))
      (node (ref "U3") (pin "46") (pinfunction "PA31/I15/SERCOM1.3/SWDIO_46") (pintype "bidirectional"))
    )
    (net (code "47") (name "TS") (class "Default")
      (node (ref "R9") (pin "1") (pinfunction "1_1") (pintype "passive"))
      (node (ref "RT1") (pin "2") (pinfunction "2_2") (pintype "passive"))
      (node (ref "U3") (pin "47") (pinfunction "PB02/I2/AIN14/SERCOM5.0/PTCX20+Y20_47") (pintype "bidirectional"))
    )
    (net (code "48") (name "TX") (class "Default")
      (node (ref "JP2") (pin "8") (pinfunction "8_8") (pintype "passive"))
      (node (ref "U3") (pin "25") (pinfunction "PA16/I2C/I0/SERCOM1.0+3.1/PTCX10+Y10_25") (pintype "bidirectional"))
    )
    (net (code "49") (name "USBID") (class "Default")
      (node (ref "J1") (pin "4") (pinfunction "ID_4") (pintype "passive"))
      (node (ref "U3") (pin "32") (pinfunction "PA23/I2C/I7/SERCOM3.1+5.0/SOF/I2SFS1/PTCX17+Y17_32") (pintype "bidirectional"))
    )
    (net (code "50") (name "USB_N") (class "Default")
      (node (ref "J1") (pin "2") (pinfunction "D-_2") (pintype "passive"))
      (node (ref "U3") (pin "33") (pinfunction "PA24/I8/SERCOM3+5.2/D-_33") (pintype "bidirectional"))
    )
    (net (code "51") (name "USB_P") (class "Default")
      (node (ref "J1") (pin "3") (pinfunction "D+_3") (pintype "passive"))
      (node (ref "U3") (pin "34") (pinfunction "PA25/19/SERCOM3+5.3/D+_34") (pintype "bidirectional"))
    )
    (net (code "52") (name "V+") (class "Default")
      (node (ref "C1") (pin "1") (pinfunction "1_1") (pintype "passive"))
      (node (ref "D1") (pin "C") (pinfunction "C_C") (pintype "passive"))
      (node (ref "Q1") (pin "2") (pinfunction "S_2") (pintype "passive"))
      (node (ref "R2") (pin "8") (pinfunction "2_8") (pintype "passive"))
      (node (ref "SJ3") (pin "1") (pinfunction "1_1") (pintype "passive"))
      (node (ref "U1") (pin "1") (pinfunction "IN_1") (pintype "power_in"))
    )
    (net (code "53") (name "VBACKUP") (class "Default")
      (node (ref "B1") (pin "+") (pinfunction "+_+") (pintype "passive"))
      (node (ref "SJ2") (pin "2") (pinfunction "2_2") (pintype "passive"))
      (node (ref "U5") (pin "14") (pinfunction "VBAT_14") (pintype "power_in"))
    )
    (net (code "54") (name "VBAT") (class "Default")
      (node (ref "C4") (pin "1") (pinfunction "1_1") (pintype "passive"))
      (node (ref "J2") (pin "1") (pinfunction "1_1") (pintype "passive"))
      (node (ref "Q1") (pin "3") (pinfunction "D_3") (pintype "passive"))
      (node (ref "R1") (pin "7") (pinfunction "2_7") (pintype "passive"))
      (node (ref "U2") (pin "3") (pinfunction "VBAT_3") (pintype "power_in"))
    )
    (net (code "55") (name "VBUS") (class "Default")
      (node (ref "CHG") (pin "A") (pinfunction "A_A") (pintype "passive"))
      (node (ref "D1") (pin "A") (pinfunction "A_A") (pintype "passive"))
      (node (ref "J1") (pin "1") (pinfunction "VUSB_1") (pintype "passive"))
      (node (ref "Q1") (pin "1") (pinfunction "G_1") (pintype "passive"))
      (node (ref "R1") (pin "8") (pinfunction "2_8") (pintype "passive"))
      (node (ref "U2") (pin "4") (pinfunction "VDD_4") (pintype "power_in"))
    )
    (net (code "56") (name "VSW") (class "Default")
      (node (ref "U3") (pin "43") (pinfunction "VSW_43") (pintype "power_in"))
    )
    (net (code "57") (name "XIN32") (class "Default")
      (node (ref "C11") (pin "1") (pinfunction "1_1") (pintype "passive"))
      (node (ref "U3") (pin "1") (pinfunction "PA00/EINT0/SERCOM1.0_1") (pintype "bidirectional"))
      (node (ref "X1") (pin "P$2") (pinfunction "P$2_P$2") (pintype "bidirectional"))
    )
    (net (code "58") (name "XOUT32") (class "Default")
      (node (ref "C12") (pin "1") (pinfunction "1_1") (pintype "passive"))
      (node (ref "U3") (pin "2") (pinfunction "PA01/EINT1/SERCOM1.1_2") (pintype "bidirectional"))
      (node (ref "X1") (pin "P$1") (pinfunction "P$1_P$1") (pintype "bidirectional"))
    )
    (net (code "59") (name "unconnected-(NEOPIX-DO-Pad3)") (class "Default")
      (node (ref "NEOPIX") (pin "3") (pinfunction "DO_3") (pintype "output"))
    )
    (net (code "60") (name "unconnected-(R1D-1-Pad4)") (class "Default")
      (node (ref "R1") (pin "4") (pinfunction "1_4") (pintype "passive"))
    )
    (net (code "61") (name "unconnected-(R2C-1-Pad3)") (class "Default")
      (node (ref "R2") (pin "3") (pinfunction "1_3") (pintype "passive"))
    )
    (net (code "62") (name "unconnected-(R2C-2-Pad6)") (class "Default")
      (node (ref "R2") (pin "6") (pinfunction "2_6") (pintype "passive"))
    )
    (net (code "63") (name "unconnected-(S1-Pad1)") (class "Default")
      (node (ref "S1") (pin "1") (pinfunction "1_1") (pintype "passive"))
    )
    (net (code "64") (name "unconnected-(U1-P4-Pad4)") (class "Default")
      (node (ref "U1") (pin "4") (pinfunction "P4_4") (pintype "bidirectional"))
    )
    (net (code "65") (name "unconnected-(U3A-PA22{slash}I2C{slash}16{slash}SERCOM3.0+5.1{slash}I2SDI{slash}PTCX16+Y16-Pad31)") (class "Default")
      (node (ref "U3") (pin "31") (pinfunction "PA22/I2C/16/SERCOM3.0+5.1/I2SDI/PTCX16+Y16_31") (pintype "bidirectional"))
    )
    (net (code "66") (name "unconnected-(U5-32KHZ-Pad1)") (class "Default")
      (node (ref "U5") (pin "1") (pinfunction "32KHZ_1") (pintype "output"))
    )
    (net (code "67") (name "unconnected-(U5-NC-Pad5)") (class "Default")
      (node (ref "U5") (pin "5") (pinfunction "NC_5") (pintype "no_connect"))
    )
    (net (code "68") (name "unconnected-(U5-NC1-Pad6)") (class "Default")
      (node (ref "U5") (pin "6") (pinfunction "NC1_6") (pintype "no_connect"))
    )
    (net (code "69") (name "unconnected-(U5-NC2-Pad7)") (class "Default")
      (node (ref "U5") (pin "7") (pinfunction "NC2_7") (pintype "no_connect"))
    )
    (net (code "70") (name "unconnected-(U5-NC3-Pad8)") (class "Default")
      (node (ref "U5") (pin "8") (pinfunction "NC3_8") (pintype "no_connect"))
    )
    (net (code "71") (name "unconnected-(U5-NC4-Pad9)") (class "Default")
      (node (ref "U5") (pin "9") (pinfunction "NC4_9") (pintype "no_connect"))
    )
    (net (code "72") (name "unconnected-(U5-NC5-Pad10)") (class "Default")
      (node (ref "U5") (pin "10") (pinfunction "NC5_10") (pintype "no_connect"))
    )
    (net (code "73") (name "unconnected-(U5-NC6-Pad11)") (class "Default")
      (node (ref "U5") (pin "11") (pinfunction "NC6_11") (pintype "no_connect"))
    )
    (net (code "74") (name "unconnected-(U5-NC7-Pad12)") (class "Default")
      (node (ref "U5") (pin "12") (pinfunction "NC7_12") (pintype "no_connect"))
    )
    (net (code "75") (name "unconnected-(U5-{slash}RST-Pad4)") (class "Default")
      (node (ref "U5") (pin "4") (pinfunction "/RST_4") (pintype "passive"))
    )
    (net (code "76") (name "~{RESET}") (class "Default")
      (node (ref "R3") (pin "8") (pinfunction "2_8") (pintype "passive"))
      (node (ref "RESET") (pin "P$2") (pinfunction "P$2_P$2") (pintype "passive"))
      (node (ref "TP5") (pin "P$1") (pinfunction "P$1_P$1") (pintype "bidirectional"))
      (node (ref "U3") (pin "40") (pinfunction "RESETN_40") (pintype "passive"))
    )
  )
)
